# Stm32F411CEU6.net
KiCad netlist of a schematic drawn in Altium Designer
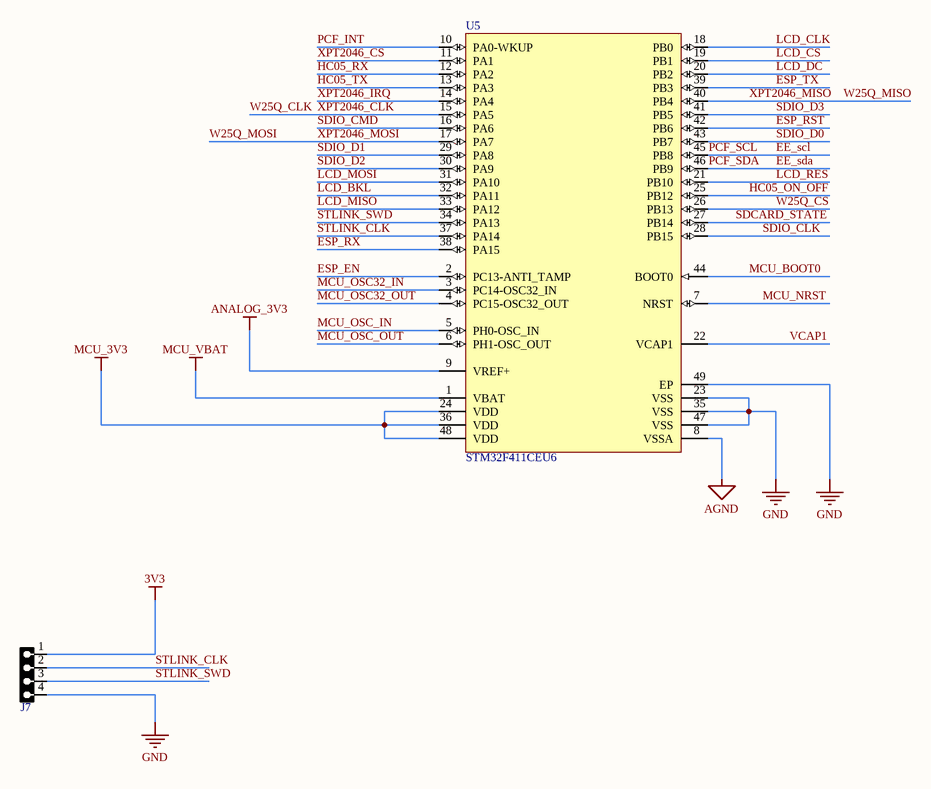
[diagram p0: Stm32F411CEU6.SchDoc]

(export (version "E")
  (design (tool "Eeschema 10.0.6"))
  (components
    (comp (ref "J7")
      (value "HDRF4")
      (footprint "HDRSE_F_1X4")
      (description "CONN, HEADER, Female, pitch: 2.54mm, 4POS")
      (libsource (lib "conn_header_2.54_st_smd_edge") (part "HDRSE_F_1X4"))
    )
    (comp (ref "U5")
      (value "STM32F411CEU6")
      (footprint "STM-UFQFPN48_M")
      (libsource (lib "STM32F411CEU6") (part "CMP-0243-00165-1"))
    )
  )
  (nets
    (net (code "1") (name "/EE_scl") (class "Default")
      (node (ref "U5") (pin "45") (pinfunction "PB8_45") (pintype "bidirectional"))
    )
    (net (code "2") (name "/EE_sda") (class "Default")
      (node (ref "U5") (pin "46") (pinfunction "PB9_46") (pintype "bidirectional"))
    )
    (net (code "3") (name "/ESP_EN") (class "Default")
      (node (ref "U5") (pin "2") (pinfunction "PC13-ANTI_TAMP_2") (pintype "bidirectional"))
    )
    (net (code "4") (name "/ESP_RST") (class "Default")
      (node (ref "U5") (pin "42") (pinfunction "PB6_42") (pintype "bidirectional"))
    )
    (net (code "5") (name "/ESP_RX") (class "Default")
      (node (ref "U5") (pin "38") (pinfunction "PA15_38") (pintype "bidirectional"))
    )
    (net (code "6") (name "/ESP_TX") (class "Default")
      (node (ref "U5") (pin "39") (pinfunction "PB3_39") (pintype "bidirectional"))
    )
    (net (code "7") (name "/HC05_ON_OFF") (class "Default")
      (node (ref "U5") (pin "25") (pinfunction "PB12_25") (pintype "bidirectional"))
    )
    (net (code "8") (name "/HC05_RX") (class "Default")
      (node (ref "U5") (pin "12") (pinfunction "PA2_12") (pintype "bidirectional"))
    )
    (net (code "9") (name "/HC05_TX") (class "Default")
      (node (ref "U5") (pin "13") (pinfunction "PA3_13") (pintype "bidirectional"))
    )
    (net (code "10") (name "/LCD_BKL") (class "Default")
      (node (ref "U5") (pin "32") (pinfunction "PA11_32") (pintype "bidirectional"))
    )
    (net (code "11") (name "/LCD_CLK") (class "Default")
      (node (ref "U5") (pin "18") (pinfunction "PB0_18") (pintype "bidirectional"))
    )
    (net (code "12") (name "/LCD_CS") (class "Default")
      (node (ref "U5") (pin "19") (pinfunction "PB1_19") (pintype "bidirectional"))
    )
    (net (code "13") (name "/LCD_DC") (class "Default")
      (node (ref "U5") (pin "20") (pinfunction "PB2_20") (pintype "bidirectional"))
    )
    (net (code "14") (name "/LCD_MISO") (class "Default")
      (node (ref "U5") (pin "33") (pinfunction "PA12_33") (pintype "bidirectional"))
    )
    (net (code "15") (name "/LCD_MOSI") (class "Default")
      (node (ref "U5") (pin "31") (pinfunction "PA10_31") (pintype "bidirectional"))
    )
    (net (code "16") (name "/LCD_RES") (class "Default")
      (node (ref "U5") (pin "21") (pinfunction "PB10_21") (pintype "bidirectional"))
    )
    (net (code "17") (name "/MCU_BOOT0") (class "Default")
      (node (ref "U5") (pin "44") (pinfunction "BOOT0_44") (pintype "input"))
    )
    (net (code "18") (name "/MCU_NRST") (class "Default")
      (node (ref "U5") (pin "7") (pinfunction "NRST_7") (pintype "bidirectional"))
    )
    (net (code "19") (name "/MCU_OSC32_IN") (class "Default")
      (node (ref "U5") (pin "3") (pinfunction "PC14-OSC32_IN_3") (pintype "bidirectional"))
    )
    (net (code "20") (name "/MCU_OSC32_OUT") (class "Default")
      (node (ref "U5") (pin "4") (pinfunction "PC15-OSC32_OUT_4") (pintype "bidirectional"))
    )
    (net (code "21") (name "/MCU_OSC_IN") (class "Default")
      (node (ref "U5") (pin "5") (pinfunction "PH0-OSC_IN_5") (pintype "bidirectional"))
    )
    (net (code "22") (name "/MCU_OSC_OUT") (class "Default")
      (node (ref "U5") (pin "6") (pinfunction "PH1-OSC_OUT_6") (pintype "bidirectional"))
    )
    (net (code "23") (name "/PCF_INT") (class "Default")
      (node (ref "U5") (pin "10") (pinfunction "PA0-WKUP_10") (pintype "bidirectional"))
    )
    (net (code "24") (name "/SDCARD_STATE") (class "Default")
      (node (ref "U5") (pin "27") (pinfunction "PB14_27") (pintype "bidirectional"))
    )
    (net (code "25") (name "/SDIO_CLK") (class "Default")
      (node (ref "U5") (pin "28") (pinfunction "PB15_28") (pintype "bidirectional"))
    )
    (net (code "26") (name "/SDIO_CMD") (class "Default")
      (node (ref "U5") (pin "16") (pinfunction "PA6_16") (pintype "bidirectional"))
    )
    (net (code "27") (name "/SDIO_D0") (class "Default")
      (node (ref "U5") (pin "43") (pinfunction "PB7_43") (pintype "bidirectional"))
    )
    (net (code "28") (name "/SDIO_D1") (class "Default")
      (node (ref "U5") (pin "29") (pinfunction "PA8_29") (pintype "bidirectional"))
    )
    (net (code "29") (name "/SDIO_D2") (class "Default")
      (node (ref "U5") (pin "30") (pinfunction "PA9_30") (pintype "bidirectional"))
    )
    (net (code "30") (name "/SDIO_D3") (class "Default")
      (node (ref "U5") (pin "41") (pinfunction "PB5_41") (pintype "bidirectional"))
    )
    (net (code "31") (name "/STLINK_CLK") (class "Default")
      (node (ref "J7") (pin "2") (pinfunction "2_2") (pintype "passive"))
      (node (ref "U5") (pin "37") (pinfunction "PA14_37") (pintype "bidirectional"))
    )
    (net (code "32") (name "/STLINK_SWD") (class "Default")
      (node (ref "J7") (pin "3") (pinfunction "3_3") (pintype "passive"))
      (node (ref "U5") (pin "34") (pinfunction "PA13_34") (pintype "bidirectional"))
    )
    (net (code "33") (name "/VCAP1") (class "Default")
      (node (ref "U5") (pin "22") (pinfunction "VCAP1_22") (pintype "passive"))
    )
    (net (code "34") (name "/W25Q_CLK") (class "Default")
      (node (ref "U5") (pin "15") (pinfunction "PA5_15") (pintype "bidirectional"))
    )
    (net (code "35") (name "/W25Q_CS") (class "Default")
      (node (ref "U5") (pin "26") (pinfunction "PB13_26") (pintype "bidirectional"))
    )
    (net (code "36") (name "/W25Q_MISO") (class "Default")
      (node (ref "U5") (pin "40") (pinfunction "PB4_40") (pintype "bidirectional"))
    )
    (net (code "37") (name "/W25Q_MOSI") (class "Default")
      (node (ref "U5") (pin "17") (pinfunction "PA7_17") (pintype "bidirectional"))
    )
    (net (code "38") (name "/XPT2046_CS") (class "Default")
      (node (ref "U5") (pin "11") (pinfunction "PA1_11") (pintype "bidirectional"))
    )
    (net (code "39") (name "/XPT2046_IRQ") (class "Default")
      (node (ref "U5") (pin "14") (pinfunction "PA4_14") (pintype "bidirectional"))
    )
    (net (code "40") (name "3V3") (class "Default")
      (node (ref "J7") (pin "1") (pinfunction "1_1") (pintype "passive"))
    )
    (net (code "41") (name "AGND") (class "Default")
      (node (ref "U5") (pin "8") (pinfunction "VSSA_8") (pintype "power_in"))
    )
    (net (code "42") (name "ANALOG_3V3") (class "Default")
      (node (ref "U5") (pin "9") (pinfunction "VREF+_9") (pintype "power_in"))
    )
    (net (code "43") (name "GND") (class "Default")
      (node (ref "J7") (pin "4") (pinfunction "4_4") (pintype "passive"))
      (node (ref "U5") (pin "23") (pinfunction "VSS_23") (pintype "power_in"))
      (node (ref "U5") (pin "35") (pinfunction "VSS_35") (pintype "power_in"))
      (node (ref "U5") (pin "47") (pinfunction "VSS_47") (pintype "power_in"))
      (node (ref "U5") (pin "49") (pinfunction "EP_49") (pintype "power_in"))
    )
    (net (code "44") (name "MCU_3V3") (class "Default")
      (node (ref "U5") (pin "24") (pinfunction "VDD_24") (pintype "power_in"))
      (node (ref "U5") (pin "36") (pinfunction "VDD_36") (pintype "power_in"))
      (node (ref "U5") (pin "48") (pinfunction "VDD_48") (pintype "power_in"))
    )
    (net (code "45") (name "MCU_VBAT") (class "Default")
      (node (ref "U5") (pin "1") (pinfunction "VBAT_1") (pintype "power_in"))
    )
  )
)
